# DSPIC33_Board_DIP_2020_09_23_A.net
KiCad netlist of a schematic drawn in EAGLE
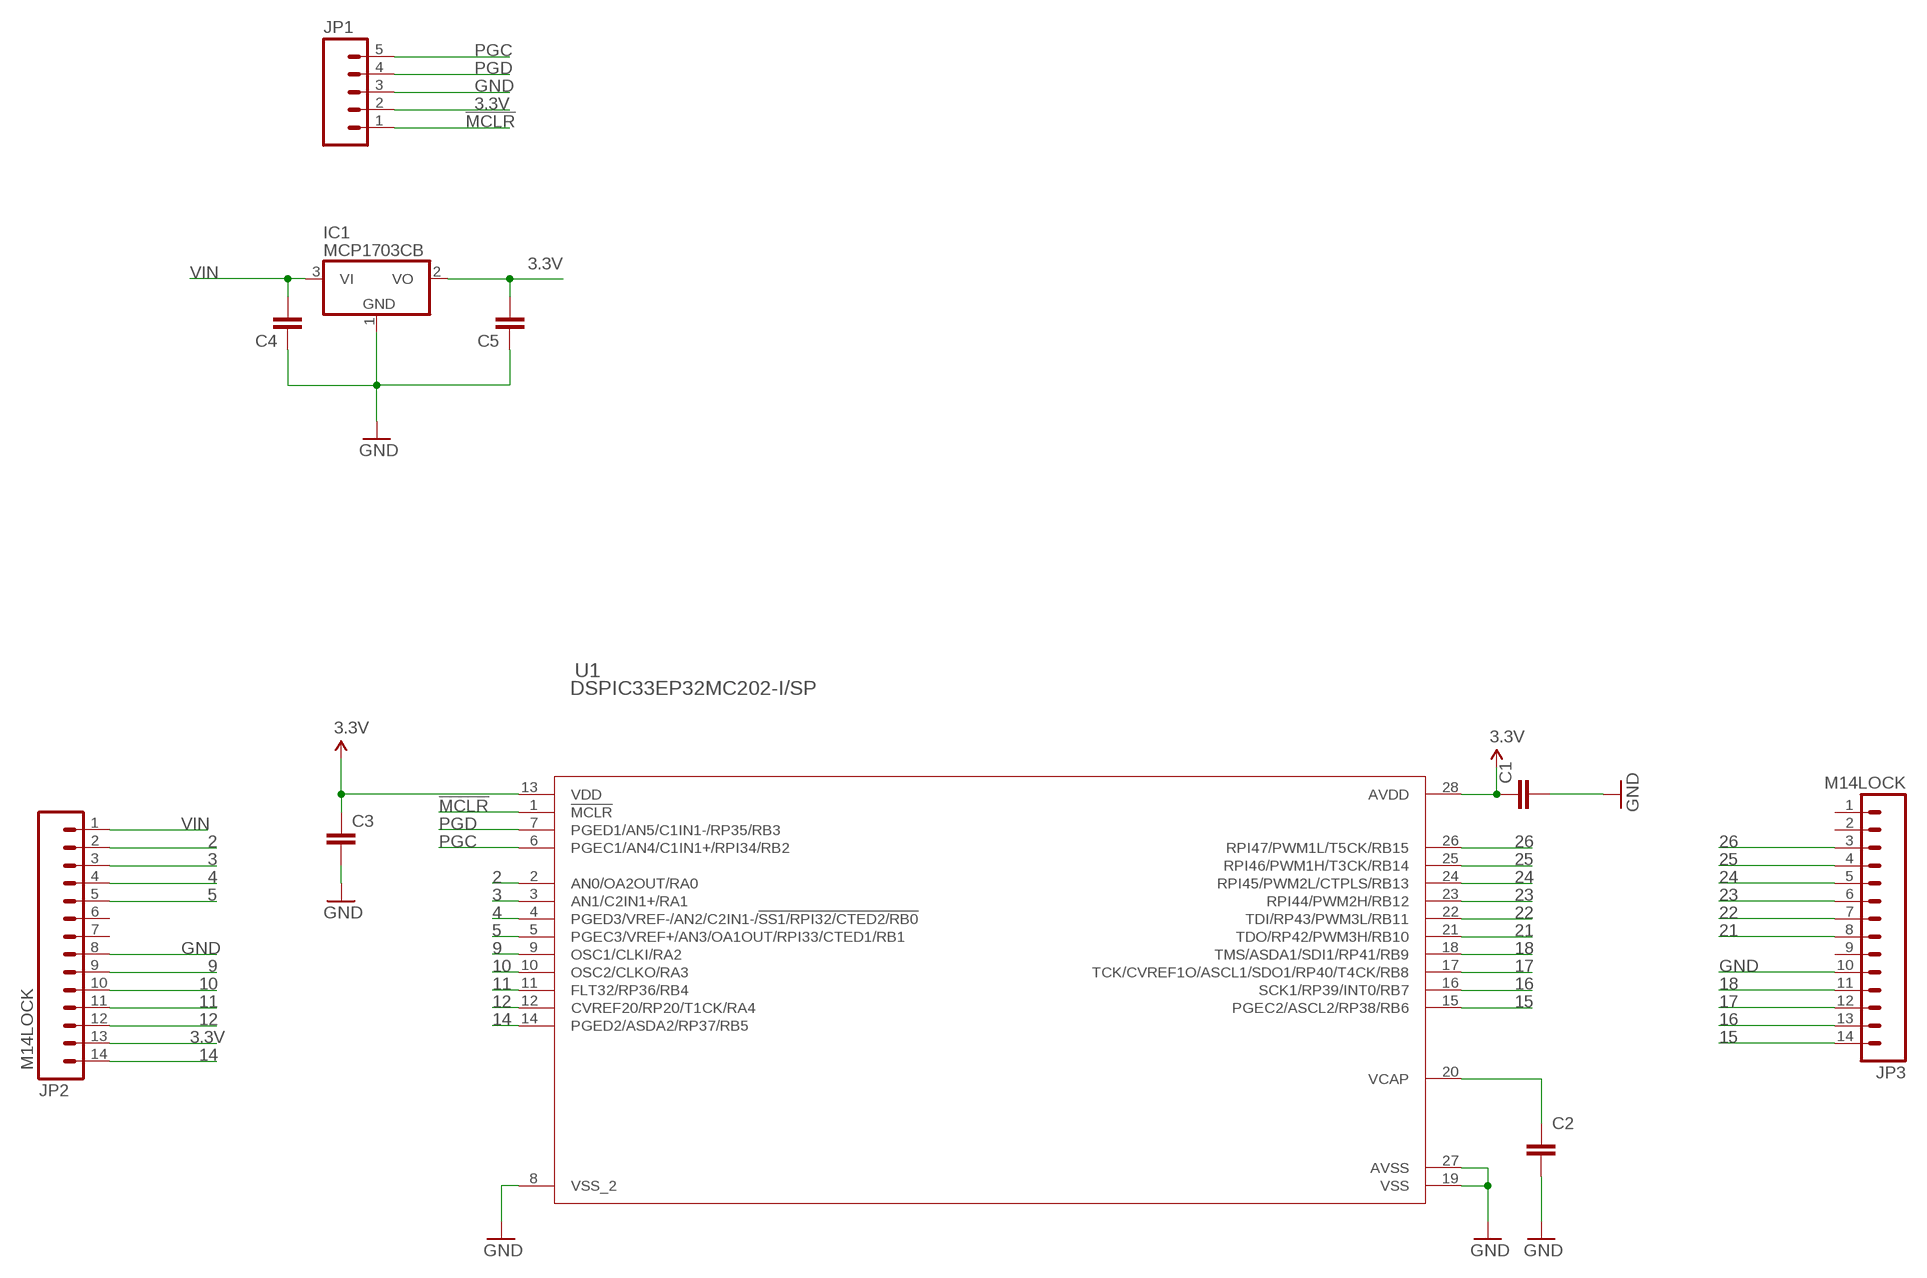
[diagram p0: schematic, sheet 1]

(export (version "E")
  (design (tool "Eeschema 10.0.6"))
  (components
    (comp (ref "C1")
      (value "CAP1206")
      (footprint "eagle-import:1206")
      (libsource (lib "eagle-import") (part "CAP1206"))
    )
    (comp (ref "C2")
      (value "CAP1206")
      (footprint "eagle-import:1206")
      (libsource (lib "eagle-import") (part "CAP1206"))
    )
    (comp (ref "C3")
      (value "CAP1206")
      (footprint "eagle-import:1206")
      (libsource (lib "eagle-import") (part "CAP1206"))
    )
    (comp (ref "C4")
      (value "CAP1206")
      (footprint "eagle-import:1206")
      (libsource (lib "eagle-import") (part "CAP1206"))
    )
    (comp (ref "C5")
      (value "CAP1206")
      (footprint "eagle-import:1206")
      (libsource (lib "eagle-import") (part "CAP1206"))
    )
    (comp (ref "IC1")
      (value "MCP1703CB")
      (footprint "eagle-import:SOT23")
      (libsource (lib "eagle-import") (part "MCP1703CB"))
    )
    (comp (ref "JP1")
      (value "M05LOCK")
      (footprint "eagle-import:1X05_LOCK")
      (libsource (lib "eagle-import") (part "M05LOCK"))
    )
    (comp (ref "JP2")
      (value "M14LOCK")
      (footprint "eagle-import:1X14_LOCK")
      (libsource (lib "eagle-import") (part "M14LOCK"))
    )
    (comp (ref "JP3")
      (value "M14LOCK")
      (footprint "eagle-import:1X14_LOCK")
      (libsource (lib "eagle-import") (part "M14LOCK"))
    )
    (comp (ref "U1")
      (value "DSPIC33EP32MC202-I/SP")
      (footprint "eagle-import:SPDIP28_300MC_MCH")
      (fields (field (name "COPYRIGHT") "Copyright (C) 2018 Accelerated Designs. All rights reserved"))
      (libsource (lib "eagle-import") (part "DSPIC33EP32MC202-I/SP"))
    )
  )
  (nets
    (net (code "1") (name "/2") (class "Default")
      (node (ref "JP2") (pin "2") (pinfunction "2_2") (pintype "passive"))
      (node (ref "U1") (pin "2") (pinfunction "AN0/OA2OUT/RA0_2") (pintype "bidirectional"))
    )
    (net (code "2") (name "/3") (class "Default")
      (node (ref "JP2") (pin "3") (pinfunction "3_3") (pintype "passive"))
      (node (ref "U1") (pin "3") (pinfunction "AN1/C2IN1+/RA1_3") (pintype "bidirectional"))
    )
    (net (code "3") (name "/4") (class "Default")
      (node (ref "JP2") (pin "4") (pinfunction "4_4") (pintype "passive"))
      (node (ref "U1") (pin "4") (pinfunction "PGED3/VREF-/AN2/C2IN1-/~{SS1/RPI32/CTED2/RB0}_4") (pintype "bidirectional"))
    )
    (net (code "4") (name "/5") (class "Default")
      (node (ref "JP2") (pin "5") (pinfunction "5_5") (pintype "passive"))
      (node (ref "U1") (pin "5") (pinfunction "PGEC3/VREF+/AN3/OA1OUT/RPI33/CTED1/RB1_5") (pintype "bidirectional"))
    )
    (net (code "5") (name "/9") (class "Default")
      (node (ref "JP2") (pin "9") (pinfunction "9_9") (pintype "passive"))
      (node (ref "U1") (pin "9") (pinfunction "OSC1/CLKI/RA2_9") (pintype "bidirectional"))
    )
    (net (code "6") (name "/10") (class "Default")
      (node (ref "JP2") (pin "10") (pinfunction "10_10") (pintype "passive"))
      (node (ref "U1") (pin "10") (pinfunction "OSC2/CLKO/RA3_10") (pintype "bidirectional"))
    )
    (net (code "7") (name "/11") (class "Default")
      (node (ref "JP2") (pin "11") (pinfunction "11_11") (pintype "passive"))
      (node (ref "U1") (pin "11") (pinfunction "FLT32/RP36/RB4_11") (pintype "bidirectional"))
    )
    (net (code "8") (name "/12") (class "Default")
      (node (ref "JP2") (pin "12") (pinfunction "12_12") (pintype "passive"))
      (node (ref "U1") (pin "12") (pinfunction "CVREF20/RP20/T1CK/RA4_12") (pintype "bidirectional"))
    )
    (net (code "9") (name "/14") (class "Default")
      (node (ref "JP2") (pin "14") (pinfunction "14_14") (pintype "passive"))
      (node (ref "U1") (pin "14") (pinfunction "PGED2/ASDA2/RP37/RB5_14") (pintype "bidirectional"))
    )
    (net (code "10") (name "/15") (class "Default")
      (node (ref "JP3") (pin "14") (pinfunction "14_14") (pintype "passive"))
      (node (ref "U1") (pin "15") (pinfunction "PGEC2/ASCL2/RP38/RB6_15") (pintype "bidirectional"))
    )
    (net (code "11") (name "/16") (class "Default")
      (node (ref "JP3") (pin "13") (pinfunction "13_13") (pintype "passive"))
      (node (ref "U1") (pin "16") (pinfunction "SCK1/RP39/INT0/RB7_16") (pintype "bidirectional"))
    )
    (net (code "12") (name "/17") (class "Default")
      (node (ref "JP3") (pin "12") (pinfunction "12_12") (pintype "passive"))
      (node (ref "U1") (pin "17") (pinfunction "TCK/CVREF1O/ASCL1/SDO1/RP40/T4CK/RB8_17") (pintype "bidirectional"))
    )
    (net (code "13") (name "/18") (class "Default")
      (node (ref "JP3") (pin "11") (pinfunction "11_11") (pintype "passive"))
      (node (ref "U1") (pin "18") (pinfunction "TMS/ASDA1/SDI1/RP41/RB9_18") (pintype "bidirectional"))
    )
    (net (code "14") (name "/21") (class "Default")
      (node (ref "JP3") (pin "8") (pinfunction "8_8") (pintype "passive"))
      (node (ref "U1") (pin "21") (pinfunction "TDO/RP42/PWM3H/RB10_21") (pintype "bidirectional"))
    )
    (net (code "15") (name "/22") (class "Default")
      (node (ref "JP3") (pin "7") (pinfunction "7_7") (pintype "passive"))
      (node (ref "U1") (pin "22") (pinfunction "TDI/RP43/PWM3L/RB11_22") (pintype "bidirectional"))
    )
    (net (code "16") (name "/23") (class "Default")
      (node (ref "JP3") (pin "6") (pinfunction "6_6") (pintype "passive"))
      (node (ref "U1") (pin "23") (pinfunction "RPI44/PWM2H/RB12_23") (pintype "bidirectional"))
    )
    (net (code "17") (name "/24") (class "Default")
      (node (ref "JP3") (pin "5") (pinfunction "5_5") (pintype "passive"))
      (node (ref "U1") (pin "24") (pinfunction "RPI45/PWM2L/CTPLS/RB13_24") (pintype "bidirectional"))
    )
    (net (code "18") (name "/25") (class "Default")
      (node (ref "JP3") (pin "4") (pinfunction "4_4") (pintype "passive"))
      (node (ref "U1") (pin "25") (pinfunction "RPI46/PWM1H/T3CK/RB14_25") (pintype "bidirectional"))
    )
    (net (code "19") (name "/26") (class "Default")
      (node (ref "JP3") (pin "3") (pinfunction "3_3") (pintype "passive"))
      (node (ref "U1") (pin "26") (pinfunction "RPI47/PWM1L/T5CK/RB15_26") (pintype "bidirectional"))
    )
    (net (code "20") (name "/PGC") (class "Default")
      (node (ref "JP1") (pin "5") (pinfunction "5_5") (pintype "passive"))
      (node (ref "U1") (pin "6") (pinfunction "PGEC1/AN4/C1IN1+/RPI34/RB2_6") (pintype "bidirectional"))
    )
    (net (code "21") (name "/PGD") (class "Default")
      (node (ref "JP1") (pin "4") (pinfunction "4_4") (pintype "passive"))
      (node (ref "U1") (pin "7") (pinfunction "PGED1/AN5/C1IN1-/RP35/RB3_7") (pintype "bidirectional"))
    )
    (net (code "22") (name "/VIN") (class "Default")
      (node (ref "C4") (pin "2") (pinfunction "2_2") (pintype "passive"))
      (node (ref "IC1") (pin "3") (pinfunction "VI_3") (pintype "input"))
      (node (ref "JP2") (pin "1") (pinfunction "1_1") (pintype "passive"))
    )
    (net (code "23") (name "/~{MCLR}") (class "Default")
      (node (ref "JP1") (pin "1") (pinfunction "1_1") (pintype "passive"))
      (node (ref "U1") (pin "1") (pinfunction "~{MCLR}_1") (pintype "bidirectional"))
    )
    (net (code "24") (name "3.3V") (class "Default")
      (node (ref "C1") (pin "1") (pinfunction "1_1") (pintype "passive"))
      (node (ref "C3") (pin "1") (pinfunction "1_1") (pintype "passive"))
      (node (ref "C5") (pin "2") (pinfunction "2_2") (pintype "passive"))
      (node (ref "IC1") (pin "2") (pinfunction "VO_2") (pintype "passive"))
      (node (ref "JP1") (pin "2") (pinfunction "2_2") (pintype "passive"))
      (node (ref "JP2") (pin "13") (pinfunction "13_13") (pintype "passive"))
      (node (ref "U1") (pin "13") (pinfunction "VDD_13") (pintype "power_in"))
      (node (ref "U1") (pin "28") (pinfunction "AVDD_28") (pintype "power_in"))
    )
    (net (code "25") (name "GND") (class "Default")
      (node (ref "C1") (pin "2") (pinfunction "2_2") (pintype "passive"))
      (node (ref "C2") (pin "1") (pinfunction "1_1") (pintype "passive"))
      (node (ref "C3") (pin "2") (pinfunction "2_2") (pintype "passive"))
      (node (ref "C4") (pin "1") (pinfunction "1_1") (pintype "passive"))
      (node (ref "C5") (pin "1") (pinfunction "1_1") (pintype "passive"))
      (node (ref "IC1") (pin "1") (pinfunction "GND_1") (pintype "passive"))
      (node (ref "JP1") (pin "3") (pinfunction "3_3") (pintype "passive"))
      (node (ref "JP2") (pin "8") (pinfunction "8_8") (pintype "passive"))
      (node (ref "JP3") (pin "10") (pinfunction "10_10") (pintype "passive"))
      (node (ref "U1") (pin "19") (pinfunction "VSS_19") (pintype "power_in"))
      (node (ref "U1") (pin "27") (pinfunction "AVSS_27") (pintype "power_in"))
      (node (ref "U1") (pin "8") (pinfunction "VSS_2_8") (pintype "power_in"))
    )
    (net (code "26") (name "Net-(U1-VCAP)") (class "Default")
      (node (ref "C2") (pin "2") (pinfunction "2_2") (pintype "passive"))
      (node (ref "U1") (pin "20") (pinfunction "VCAP_20") (pintype "power_in"))
    )
    (net (code "27") (name "unconnected-(JP2-Pad6)") (class "Default")
      (node (ref "JP2") (pin "6") (pinfunction "6_6") (pintype "passive"))
    )
    (net (code "28") (name "unconnected-(JP2-Pad7)") (class "Default")
      (node (ref "JP2") (pin "7") (pinfunction "7_7") (pintype "passive"))
    )
    (net (code "29") (name "unconnected-(JP3-Pad1)") (class "Default")
      (node (ref "JP3") (pin "1") (pinfunction "1_1") (pintype "passive"))
    )
    (net (code "30") (name "unconnected-(JP3-Pad2)") (class "Default")
      (node (ref "JP3") (pin "2") (pinfunction "2_2") (pintype "passive"))
    )
    (net (code "31") (name "unconnected-(JP3-Pad9)") (class "Default")
      (node (ref "JP3") (pin "9") (pinfunction "9_9") (pintype "passive"))
    )
  )
)
